# SCH_ESP-CellCore_USB_Interlock_RevA3.net
KiCad netlist of a schematic drawn in EasyEDA
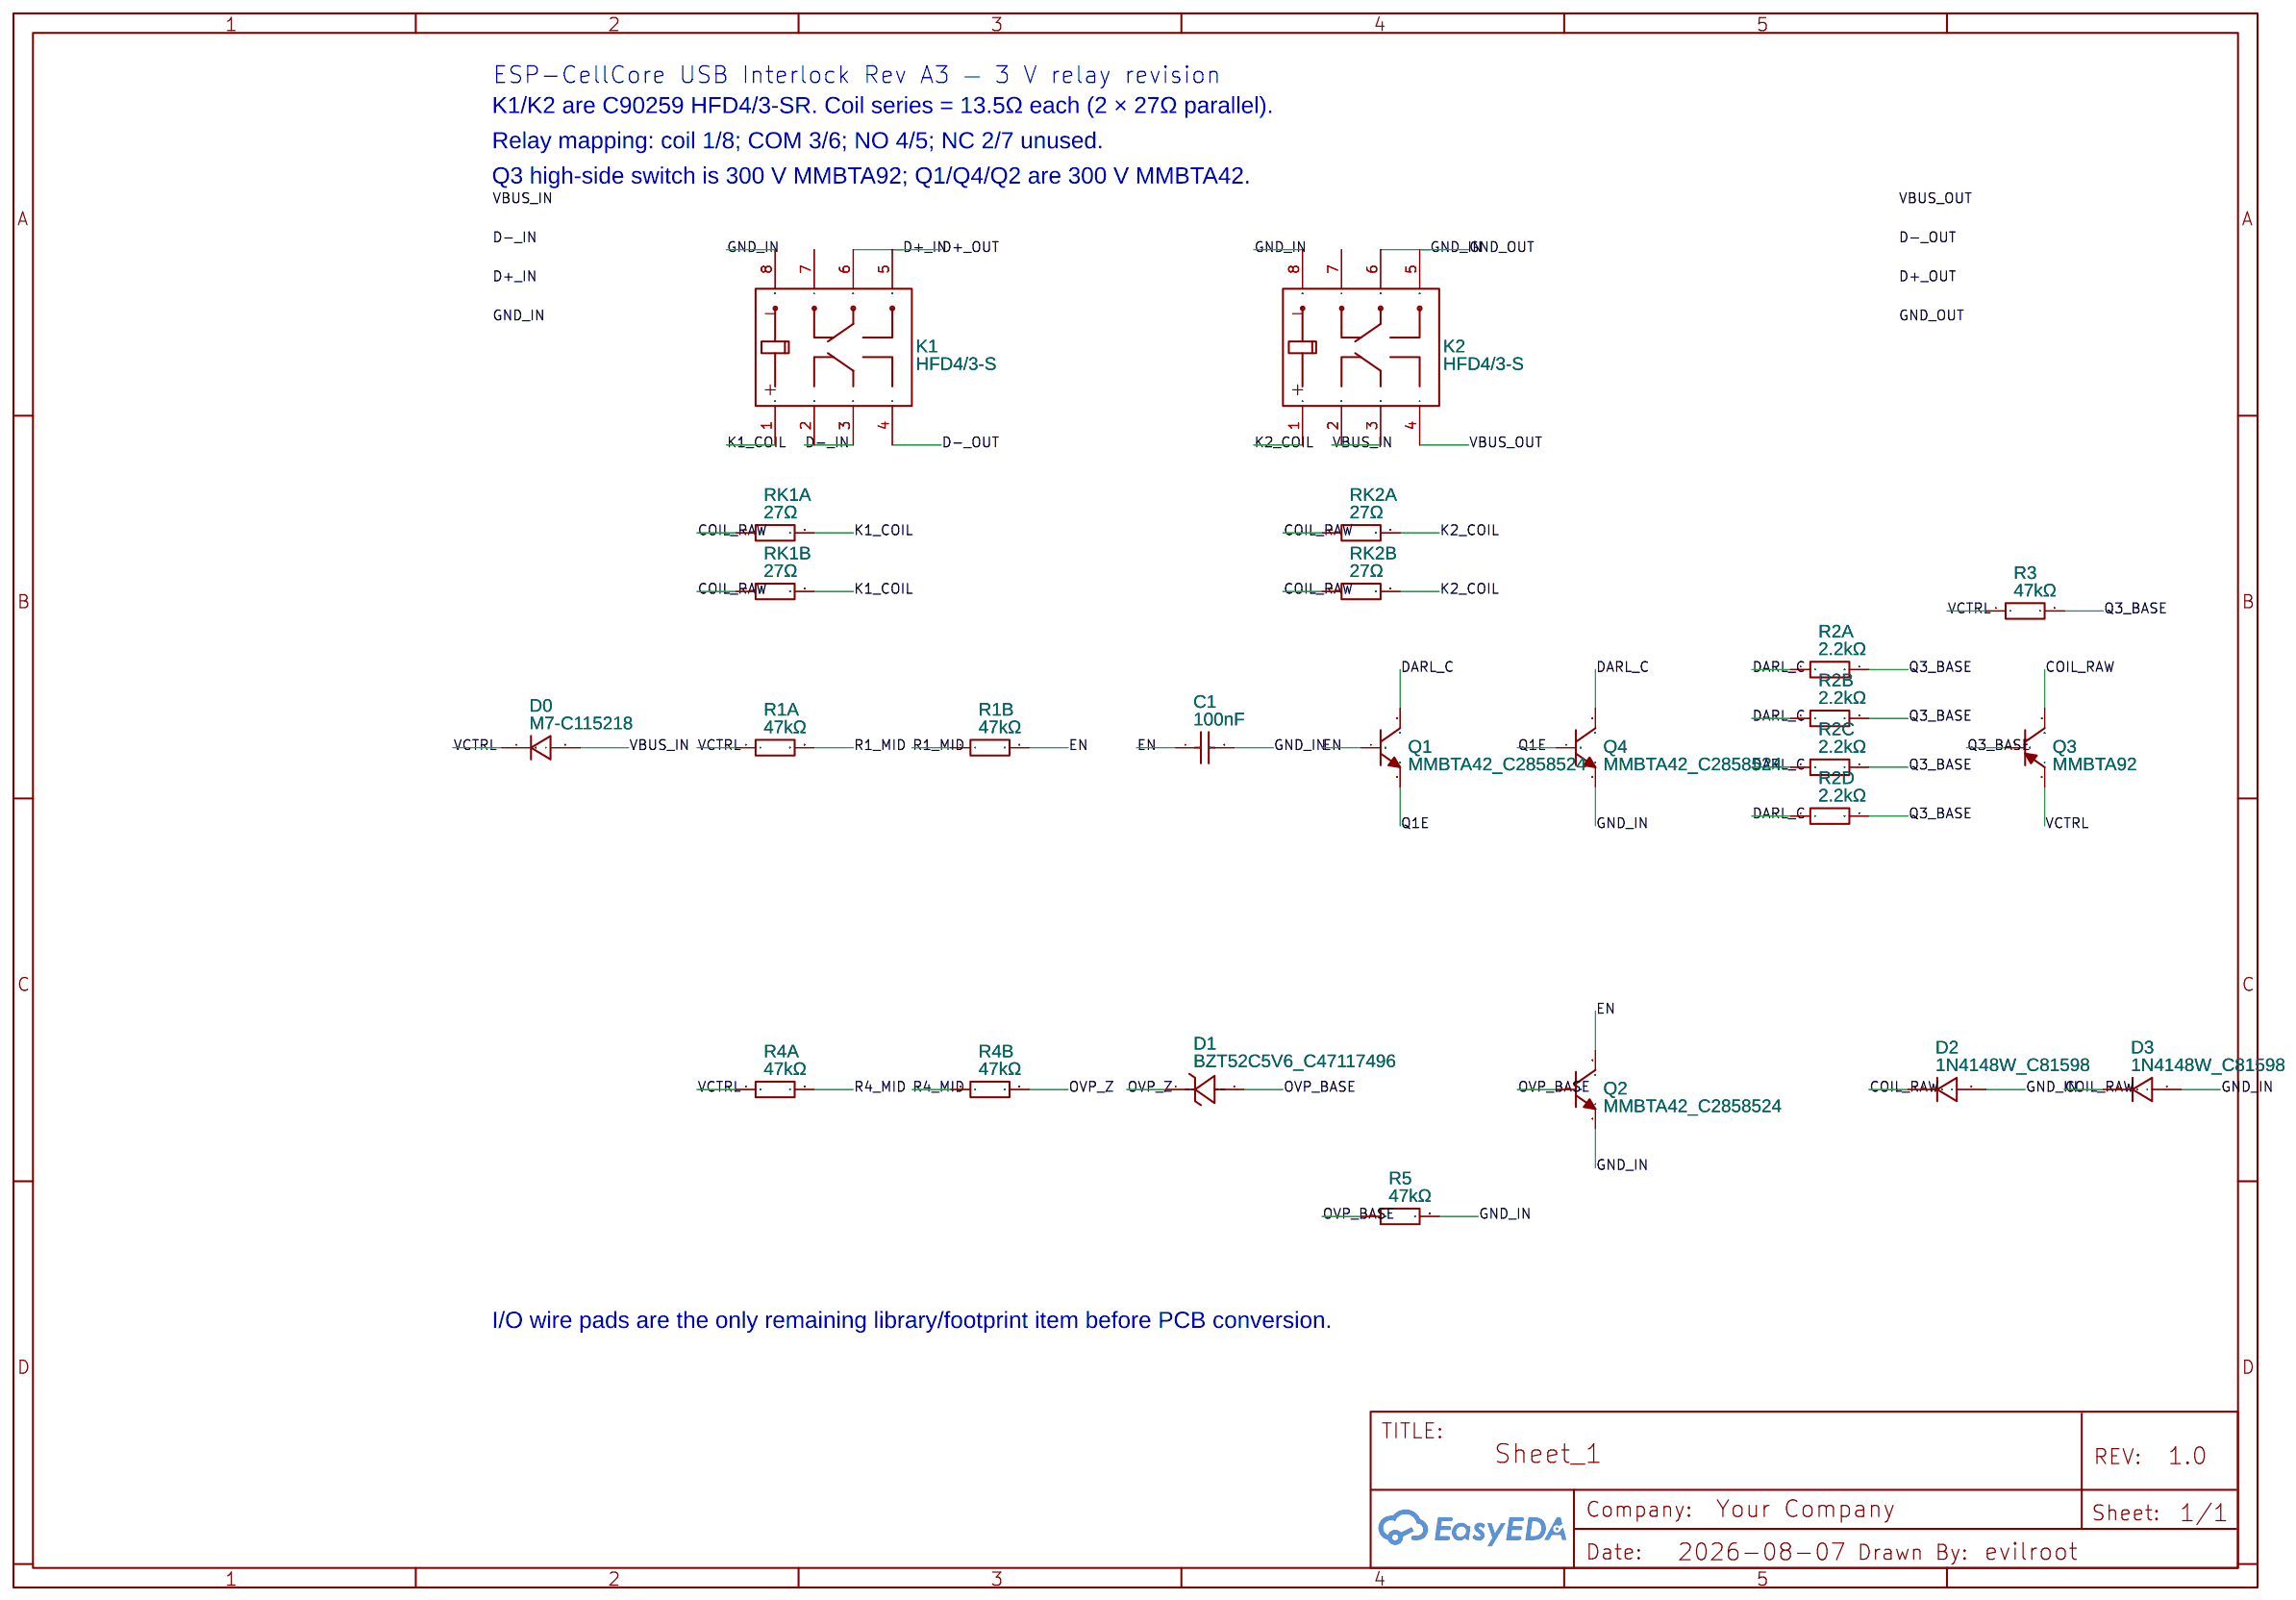
[diagram p0: schematic sheet]

(export (version "E")
  (design (tool "Eeschema 10.0.6"))
  (components
    (comp (ref "C1")
      (value "100nF")
      (fields
        (field (name "Manufacturer Part") "C0805C104K5RAC7800")
        (field (name "Manufacturer") "KEMET(基美)")
      )
      (libsource (lib "") (part "C0805C104K5RACTU"))
    )
    (comp (ref "D0")
      (value "M7-C115218")
      (fields (field (name "Manufacturer Part") "M7") (field (name "Manufacturer") "晶导微电子"))
      (libsource (lib "") (part "M7-C115218"))
    )
    (comp (ref "D1")
      (value "BZT52C5V6_C47117496")
      (fields (field (name "Manufacturer Part") "BZT52C5V6") (field (name "Manufacturer") "baocheng(宝乘)"))
      (libsource (lib "") (part "BZT52C5V6_C47117496"))
    )
    (comp (ref "D2")
      (value "1N4148W_C81598")
      (fields (field (name "Manufacturer Part") "1N4148W") (field (name "Manufacturer") "ST(先科)"))
      (libsource (lib "") (part "1N4148W_C81598"))
    )
    (comp (ref "D3")
      (value "1N4148W_C81598")
      (fields (field (name "Manufacturer Part") "1N4148W") (field (name "Manufacturer") "ST(先科)"))
      (libsource (lib "") (part "1N4148W_C81598"))
    )
    (comp (ref "K1")
      (value "HFD4/3-S")
      (fields (field (name "Manufacturer Part") "HFD4/3-SR") (field (name "Manufacturer") "HF(宏发)"))
      (libsource (lib "") (part "HFD4/3-S"))
    )
    (comp (ref "K2")
      (value "HFD4/3-S")
      (fields (field (name "Manufacturer Part") "HFD4/3-SR") (field (name "Manufacturer") "HF(宏发)"))
      (libsource (lib "") (part "HFD4/3-S"))
    )
    (comp (ref "Q1")
      (value "MMBTA42_C2858524")
      (fields (field (name "Manufacturer Part") "MMBTA42") (field (name "Manufacturer") "MDD(辰达半导体)"))
      (libsource (lib "") (part "MMBTA42_C2858524"))
    )
    (comp (ref "Q2")
      (value "MMBTA42_C2858524")
      (fields (field (name "Manufacturer Part") "MMBTA42") (field (name "Manufacturer") "MDD(辰达半导体)"))
      (libsource (lib "") (part "MMBTA42_C2858524"))
    )
    (comp (ref "Q3")
      (value "MMBTA92")
      (fields (field (name "Manufacturer") "GOODWORK(固得沃克)"))
      (libsource (lib "") (part "MMBTA92"))
    )
    (comp (ref "Q4")
      (value "MMBTA42_C2858524")
      (fields (field (name "Manufacturer Part") "MMBTA42") (field (name "Manufacturer") "MDD(辰达半导体)"))
      (libsource (lib "") (part "MMBTA42_C2858524"))
    )
    (comp (ref "R1A")
      (value "47kΩ")
      (fields (field (name "Manufacturer Part") "AC0805FR-0747KL") (field (name "Manufacturer") "YAGEO(国巨)"))
      (libsource (lib "") (part "AC0805FR-0747KL_2"))
    )
    (comp (ref "R1B")
      (value "47kΩ")
      (fields (field (name "Manufacturer Part") "AC0805FR-0747KL") (field (name "Manufacturer") "YAGEO(国巨)"))
      (libsource (lib "") (part "AC0805FR-0747KL_1"))
    )
    (comp (ref "R2A")
      (value "2.2kΩ")
      (fields
        (field (name "Manufacturer Part") "0805W8F2201T5E")
        (field (name "Manufacturer") "UNI-ROYAL(厚声)")
      )
      (libsource (lib "") (part "0805W8F2201T5E"))
    )
    (comp (ref "R2B")
      (value "2.2kΩ")
      (fields
        (field (name "Manufacturer Part") "0805W8F2201T5E")
        (field (name "Manufacturer") "UNI-ROYAL(厚声)")
      )
      (libsource (lib "") (part "0805W8F2201T5E_3"))
    )
    (comp (ref "R2C")
      (value "2.2kΩ")
      (fields
        (field (name "Manufacturer Part") "0805W8F2201T5E")
        (field (name "Manufacturer") "UNI-ROYAL(厚声)")
      )
      (libsource (lib "") (part "0805W8F2201T5E_2"))
    )
    (comp (ref "R2D")
      (value "2.2kΩ")
      (fields
        (field (name "Manufacturer Part") "0805W8F2201T5E")
        (field (name "Manufacturer") "UNI-ROYAL(厚声)")
      )
      (libsource (lib "") (part "0805W8F2201T5E_1"))
    )
    (comp (ref "R3")
      (value "47kΩ")
      (fields (field (name "Manufacturer Part") "AC0805FR-0747KL") (field (name "Manufacturer") "YAGEO(国巨)"))
      (libsource (lib "") (part "AC0805FR-0747KL"))
    )
    (comp (ref "R4A")
      (value "47kΩ")
      (fields (field (name "Manufacturer Part") "AC0805FR-0747KL") (field (name "Manufacturer") "YAGEO(国巨)"))
      (libsource (lib "") (part "AC0805FR-0747KL_4"))
    )
    (comp (ref "R4B")
      (value "47kΩ")
      (fields (field (name "Manufacturer Part") "AC0805FR-0747KL") (field (name "Manufacturer") "YAGEO(国巨)"))
      (libsource (lib "") (part "AC0805FR-0747KL_3"))
    )
    (comp (ref "R5")
      (value "47kΩ")
      (fields (field (name "Manufacturer Part") "AC0805FR-0747KL") (field (name "Manufacturer") "YAGEO(国巨)"))
      (libsource (lib "") (part "AC0805FR-0747KL"))
    )
    (comp (ref "RK1A")
      (value "27Ω")
      (fields (field (name "Manufacturer Part") "CR0805F827R0G") (field (name "Manufacturer") "LIZ(丽智电子)"))
      (libsource (lib "") (part "CR0805F827R0G"))
    )
    (comp (ref "RK1B")
      (value "27Ω")
      (fields (field (name "Manufacturer Part") "CR0805F827R0G") (field (name "Manufacturer") "LIZ(丽智电子)"))
      (libsource (lib "") (part "CR0805F827R0G_1"))
    )
    (comp (ref "RK2A")
      (value "27Ω")
      (fields (field (name "Manufacturer Part") "CR0805F827R0G") (field (name "Manufacturer") "LIZ(丽智电子)"))
      (libsource (lib "") (part "CR0805F827R0G_2"))
    )
    (comp (ref "RK2B")
      (value "27Ω")
      (fields (field (name "Manufacturer Part") "CR0805F827R0G") (field (name "Manufacturer") "LIZ(丽智电子)"))
      (libsource (lib "") (part "CR0805F827R0G_3"))
    )
  )
  (nets
    (net (code "1") (name "/COIL_RAW") (class "Default")
      (node (ref "D2") (pin "1") (pinfunction "K_1") (pintype "unspecified"))
      (node (ref "D3") (pin "1") (pinfunction "K_1") (pintype "unspecified"))
      (node (ref "Q3") (pin "3") (pinfunction "C_3") (pintype "input"))
      (node (ref "RK1A") (pin "1") (pinfunction "1_1") (pintype "input"))
      (node (ref "RK1B") (pin "1") (pinfunction "1_1") (pintype "input"))
      (node (ref "RK2A") (pin "1") (pinfunction "1_1") (pintype "input"))
      (node (ref "RK2B") (pin "1") (pinfunction "1_1") (pintype "input"))
    )
    (net (code "2") (name "/D+_IN") (class "Default")
      (node (ref "K1") (pin "5") (pinfunction "5_5") (pintype "input"))
      (node (ref "K1") (pin "6") (pinfunction "6_6") (pintype "input"))
    )
    (net (code "3") (name "/D-_IN") (class "Default")
      (node (ref "K1") (pin "3") (pinfunction "3_3") (pintype "input"))
    )
    (net (code "4") (name "/D-_OUT") (class "Default")
      (node (ref "K1") (pin "4") (pinfunction "4_4") (pintype "input"))
    )
    (net (code "5") (name "/DARL_C") (class "Default")
      (node (ref "Q1") (pin "3") (pinfunction "C_3") (pintype "input"))
      (node (ref "Q4") (pin "3") (pinfunction "C_3") (pintype "input"))
      (node (ref "R2A") (pin "1") (pinfunction "1_1") (pintype "input"))
      (node (ref "R2B") (pin "1") (pinfunction "1_1") (pintype "input"))
      (node (ref "R2C") (pin "1") (pinfunction "1_1") (pintype "input"))
      (node (ref "R2D") (pin "1") (pinfunction "1_1") (pintype "input"))
    )
    (net (code "6") (name "/EN") (class "Default")
      (node (ref "C1") (pin "1") (pinfunction "1_1") (pintype "input"))
      (node (ref "Q1") (pin "1") (pinfunction "B_1") (pintype "input"))
      (node (ref "Q2") (pin "3") (pinfunction "C_3") (pintype "input"))
      (node (ref "R1B") (pin "2") (pinfunction "2_2") (pintype "unspecified"))
    )
    (net (code "7") (name "/GND_IN") (class "Default")
      (node (ref "C1") (pin "2") (pinfunction "2_2") (pintype "input"))
      (node (ref "D2") (pin "2") (pinfunction "A_2") (pintype "unspecified"))
      (node (ref "D3") (pin "2") (pinfunction "A_2") (pintype "unspecified"))
      (node (ref "K1") (pin "8") (pinfunction "8_8") (pintype "input"))
      (node (ref "K2") (pin "5") (pinfunction "5_5") (pintype "input"))
      (node (ref "K2") (pin "6") (pinfunction "6_6") (pintype "input"))
      (node (ref "K2") (pin "8") (pinfunction "8_8") (pintype "input"))
      (node (ref "Q2") (pin "2") (pinfunction "E_2") (pintype "input"))
      (node (ref "Q4") (pin "2") (pinfunction "E_2") (pintype "input"))
      (node (ref "R5") (pin "2") (pinfunction "2_2") (pintype "unspecified"))
    )
    (net (code "8") (name "/K1_COIL") (class "Default")
      (node (ref "K1") (pin "1") (pinfunction "1_1") (pintype "input"))
      (node (ref "RK1A") (pin "2") (pinfunction "2_2") (pintype "input"))
      (node (ref "RK1B") (pin "2") (pinfunction "2_2") (pintype "input"))
    )
    (net (code "9") (name "/K2_COIL") (class "Default")
      (node (ref "K2") (pin "1") (pinfunction "1_1") (pintype "input"))
      (node (ref "RK2A") (pin "2") (pinfunction "2_2") (pintype "input"))
      (node (ref "RK2B") (pin "2") (pinfunction "2_2") (pintype "input"))
    )
    (net (code "10") (name "/OVP_BASE") (class "Default")
      (node (ref "D1") (pin "2") (pinfunction "A_2") (pintype "unspecified"))
      (node (ref "Q2") (pin "1") (pinfunction "B_1") (pintype "input"))
      (node (ref "R5") (pin "1") (pinfunction "1_1") (pintype "unspecified"))
    )
    (net (code "11") (name "/OVP_Z") (class "Default")
      (node (ref "D1") (pin "1") (pinfunction "C_1") (pintype "unspecified"))
      (node (ref "R4B") (pin "2") (pinfunction "2_2") (pintype "unspecified"))
    )
    (net (code "12") (name "/Q1E") (class "Default")
      (node (ref "Q1") (pin "2") (pinfunction "E_2") (pintype "input"))
      (node (ref "Q4") (pin "1") (pinfunction "B_1") (pintype "input"))
    )
    (net (code "13") (name "/Q3_BASE") (class "Default")
      (node (ref "Q3") (pin "1") (pinfunction "B_1") (pintype "input"))
      (node (ref "R2A") (pin "2") (pinfunction "2_2") (pintype "input"))
      (node (ref "R2B") (pin "2") (pinfunction "2_2") (pintype "input"))
      (node (ref "R2C") (pin "2") (pinfunction "2_2") (pintype "input"))
      (node (ref "R2D") (pin "2") (pinfunction "2_2") (pintype "input"))
      (node (ref "R3") (pin "2") (pinfunction "2_2") (pintype "unspecified"))
    )
    (net (code "14") (name "/R1_MID") (class "Default")
      (node (ref "R1A") (pin "2") (pinfunction "2_2") (pintype "unspecified"))
      (node (ref "R1B") (pin "1") (pinfunction "1_1") (pintype "unspecified"))
    )
    (net (code "15") (name "/R4_MID") (class "Default")
      (node (ref "R4A") (pin "2") (pinfunction "2_2") (pintype "unspecified"))
      (node (ref "R4B") (pin "1") (pinfunction "1_1") (pintype "unspecified"))
    )
    (net (code "16") (name "/VBUS_IN") (class "Default")
      (node (ref "D0") (pin "2") (pinfunction "A_2") (pintype "unspecified"))
      (node (ref "K2") (pin "3") (pinfunction "3_3") (pintype "input"))
    )
    (net (code "17") (name "/VBUS_OUT") (class "Default")
      (node (ref "K2") (pin "4") (pinfunction "4_4") (pintype "input"))
    )
    (net (code "18") (name "/VCTRL") (class "Default")
      (node (ref "D0") (pin "1") (pinfunction "C_1") (pintype "unspecified"))
      (node (ref "Q3") (pin "2") (pinfunction "E_2") (pintype "input"))
      (node (ref "R1A") (pin "1") (pinfunction "1_1") (pintype "unspecified"))
      (node (ref "R3") (pin "1") (pinfunction "1_1") (pintype "unspecified"))
      (node (ref "R4A") (pin "1") (pinfunction "1_1") (pintype "unspecified"))
    )
    (net (code "19") (name "unconnected-(K1-Pad2)") (class "Default")
      (node (ref "K1") (pin "2") (pinfunction "2_2") (pintype "input"))
    )
    (net (code "20") (name "unconnected-(K1-Pad7)") (class "Default")
      (node (ref "K1") (pin "7") (pinfunction "7_7") (pintype "input"))
    )
    (net (code "21") (name "unconnected-(K2-Pad2)") (class "Default")
      (node (ref "K2") (pin "2") (pinfunction "2_2") (pintype "input"))
    )
    (net (code "22") (name "unconnected-(K2-Pad7)") (class "Default")
      (node (ref "K2") (pin "7") (pinfunction "7_7") (pintype "input"))
    )
  )
)
